# CON_MINI_USBB_RA_KME04-USBMU03A01-1.net
KiCad netlist of a schematic drawn in Altium Designer
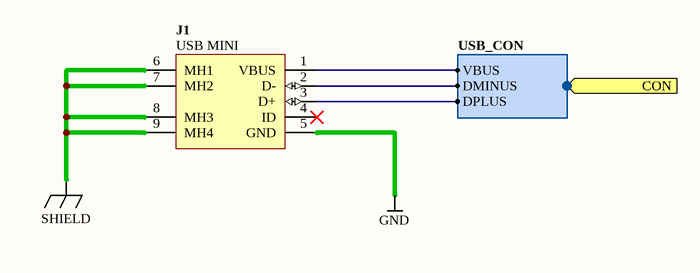
[diagram p0: CON_MINI_USBB_RA_KME04-USBMU03A01-1.SchDoc]

(export (version "E")
  (design (tool "Eeschema 10.0.6"))
  (components
    (comp (ref "J1")
      (value "USB MINI")
      (footprint "USB-MOLEX-675031020")
      (description "USB, MINI, SMD,  Molex")
      (libsource (lib "AltiumDesignLibrary") (part "048190-0001"))
    )
  )
  (nets
    (net (code "2") (name "/DMINUS") (class "Default")
      (node (ref "J1") (pin "2") (pinfunction "D-_2") (pintype "bidirectional"))
    )
    (net (code "3") (name "/DPLUS") (class "Default")
      (node (ref "J1") (pin "3") (pinfunction "D+_3") (pintype "bidirectional"))
    )
    (net (code "4") (name "/VBUS") (class "Default")
      (node (ref "J1") (pin "1") (pinfunction "VBUS_1") (pintype "power_in"))
    )
    (net (code "6") (name "GND") (class "Default")
      (node (ref "J1") (pin "5") (pinfunction "GND_5") (pintype "power_in"))
    )
    (net (code "7") (name "SHIELD") (class "Default")
      (node (ref "J1") (pin "6") (pinfunction "MH1_6") (pintype "passive"))
      (node (ref "J1") (pin "7") (pinfunction "MH2_7") (pintype "passive"))
      (node (ref "J1") (pin "8") (pinfunction "MH3_8") (pintype "passive"))
      (node (ref "J1") (pin "9") (pinfunction "MH4_9") (pintype "passive"))
    )
    (net (code "8") (name "unconnected-(J1-ID-Pad4)") (class "Default")
      (node (ref "J1") (pin "4") (pinfunction "ID_4") (pintype "passive+no_connect"))
    )
  )
)
